# Power_System.net
KiCad netlist of a schematic drawn in Altium Designer
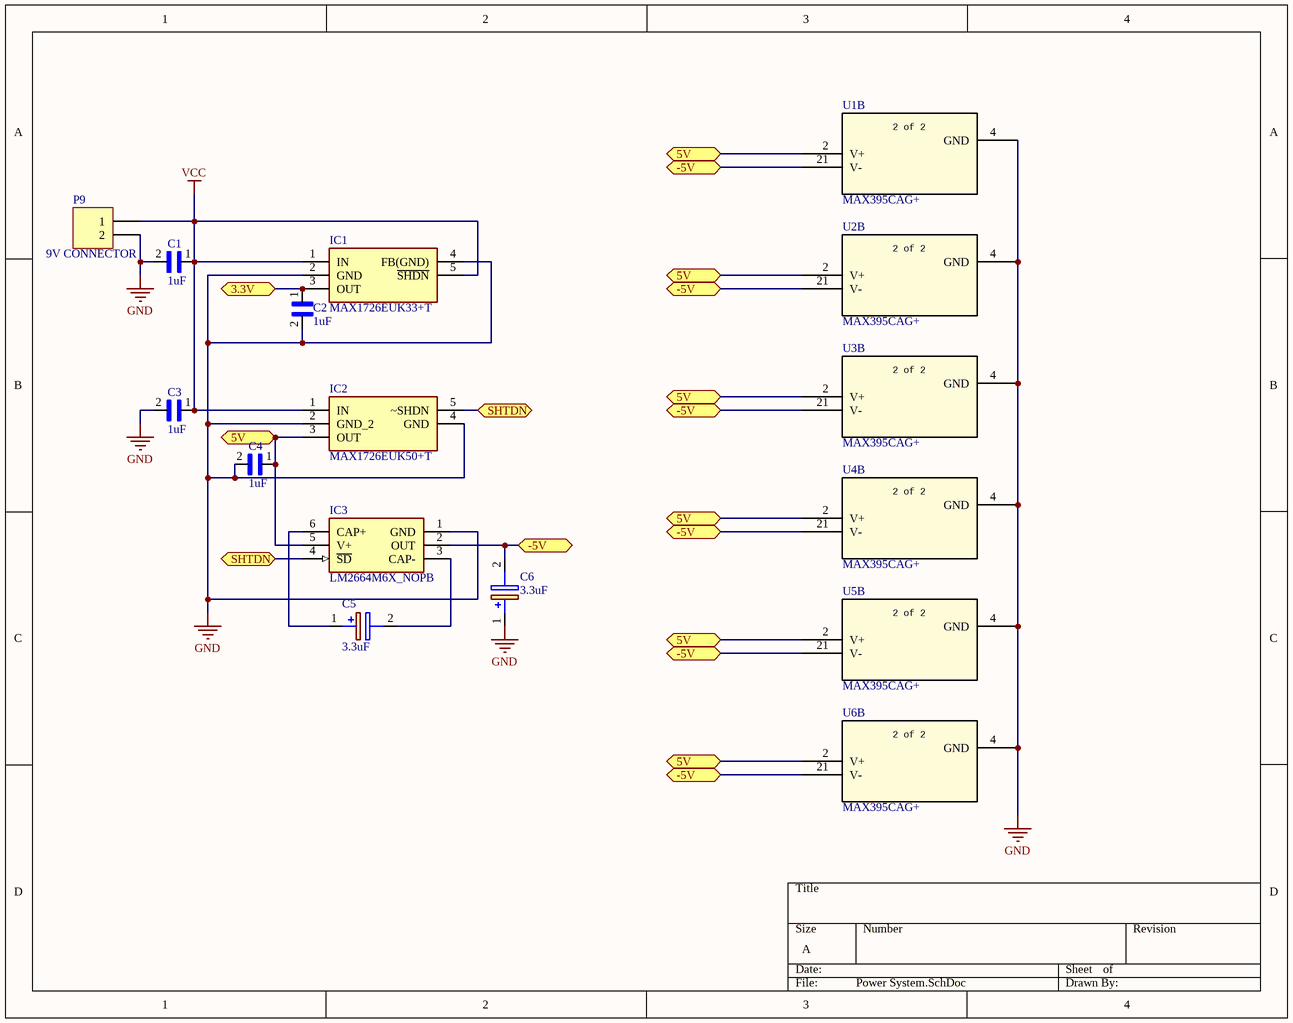
[diagram p0: Power System.SchDoc]

(export (version "E")
  (design (tool "Eeschema 10.0.6"))
  (components
    (comp (ref "C1")
      (value "1uF")
      (footprint "CAPC2012X135N")
      (description "1ÂµF Â±10% 25V Ceramic Capacitor X7R 0805 _2012 Metric_")
      (fields (field (name "DIGI-KEY_PART_NUMBER") "587-6357-1-ND") (field (name "MF") "Taiyo Yuden"))
      (libsource (lib "TMK212B7105KGHTR") (part "TMK212B7105KGHTR"))
    )
    (comp (ref "C2")
      (value "1uF")
      (footprint "CAPC2012X135N")
      (description "1ÂµF Â±10% 25V Ceramic Capacitor X7R 0805 _2012 Metric_")
      (fields (field (name "DIGI-KEY_PART_NUMBER") "587-6357-1-ND") (field (name "MF") "Taiyo Yuden"))
      (libsource (lib "") (part "TMK212B7105KGHTR_1"))
    )
    (comp (ref "C3")
      (value "1uF")
      (footprint "CAPC2012X135N")
      (description "1ÂµF Â±10% 25V Ceramic Capacitor X7R 0805 _2012 Metric_")
      (fields (field (name "DIGI-KEY_PART_NUMBER") "587-6357-1-ND") (field (name "MF") "Taiyo Yuden"))
      (libsource (lib "TMK212B7105KGHTR") (part "TMK212B7105KGHTR"))
    )
    (comp (ref "C4")
      (value "1uF")
      (footprint "CAPC2012X135N")
      (description "1ÂµF Â±10% 25V Ceramic Capacitor X7R 0805 _2012 Metric_")
      (fields (field (name "DIGI-KEY_PART_NUMBER") "587-6357-1-ND") (field (name "MF") "Taiyo Yuden"))
      (libsource (lib "TMK212B7105KGHTR") (part "TMK212B7105KGHTR"))
    )
    (comp (ref "C5")
      (value "3.3uF")
      (footprint "SamacSys:CAPAE430X550N")
      (description "Capacitor Polarised")
      (fields
        (field (name "MANUFACTURER_PART_NUMBER") "16SVP3R3M")
        (field (name "MOUSER PART NUMBER") "667-16SVP3R3M")
      )
      (libsource (lib "*") (part "16SVP3R3M"))
    )
    (comp (ref "C6")
      (value "3.3uF")
      (footprint "SamacSys:CAPAE430X550N")
      (description "Capacitor Polarised")
      (fields
        (field (name "MANUFACTURER_PART_NUMBER") "16SVP3R3M")
        (field (name "MOUSER PART NUMBER") "667-16SVP3R3M")
      )
      (libsource (lib "") (part "16SVP3R3M_1"))
    )
    (comp (ref "IC1")
      (value "MAX1726EUK33+T")
      (footprint "SamacSys:SOT95P280X145-5N")
      (description "Integrated Circuit")
      (fields (field (name "MOUSER PART NUMBER") "700-MAX1726EUK33T"))
      (libsource (lib "*") (part "MAX1726EUK33+T"))
    )
    (comp (ref "IC2")
      (value "MAX1726EUK50+T")
      (footprint "SamacSys:SOT95P280X145-5N")
      (description "Integrated Circuit")
      (fields (field (name "MOUSER PART NUMBER") "700-MAX1726EUK50T"))
      (libsource (lib "*") (part "MAX1726EUK50+T"))
    )
    (comp (ref "IC3")
      (value "LM2664M6X_NOPB")
      (footprint "SamacSys:SOT95P280X145-6N")
      (description "Integrated Circuit")
      (fields
        (field (name "MANUFACTURER_PART_NUMBER") "LM2664M6X/NOPB")
        (field (name "MOUSER PART NUMBER") "926-LM2664M6X/NOPB")
      )
      (libsource (lib "*") (part "LM2664M6X_NOPB"))
    )
    (comp (ref "P9")
      (value "9V CONNECTOR")
      (footprint "HDR1X2")
      (description "Header, 2-Pin")
      (fields (field (name "PUBLISHER") "Altium Limited"))
      (libsource (lib "Miscellaneous Connectors") (part "Header 2"))
    )
    (comp (ref "U1")
      (value "MAX395CAG+")
      (footprint "21-0056C_24_MXM")
      (description "No Description Available")
      (fields (field (name "COPYRIGHT") "Copyright (C) 2018 Accelerated Designs. All rights reserved"))
      (libsource (lib "MAX395") (part "MAX395CAG+"))
    )
    (comp (ref "U2")
      (value "MAX395CAG+")
      (footprint "21-0056C_24_MXM")
      (description "No Description Available")
      (fields (field (name "COPYRIGHT") "Copyright (C) 2018 Accelerated Designs. All rights reserved"))
      (libsource (lib "MAX395") (part "MAX395CAG+"))
    )
    (comp (ref "U3")
      (value "MAX395CAG+")
      (footprint "21-0056C_24_MXM")
      (description "No Description Available")
      (fields (field (name "COPYRIGHT") "Copyright (C) 2018 Accelerated Designs. All rights reserved"))
      (libsource (lib "MAX395") (part "MAX395CAG+"))
    )
    (comp (ref "U4")
      (value "MAX395CAG+")
      (footprint "21-0056C_24_MXM")
      (description "No Description Available")
      (fields (field (name "COPYRIGHT") "Copyright (C) 2018 Accelerated Designs. All rights reserved"))
      (libsource (lib "MAX395") (part "MAX395CAG+"))
    )
    (comp (ref "U5")
      (value "MAX395CAG+")
      (footprint "21-0056C_24_MXM")
      (description "No Description Available")
      (fields (field (name "COPYRIGHT") "Copyright (C) 2018 Accelerated Designs. All rights reserved"))
      (libsource (lib "MAX395") (part "MAX395CAG+"))
    )
    (comp (ref "U6")
      (value "MAX395CAG+")
      (footprint "21-0056C_24_MXM")
      (description "No Description Available")
      (fields (field (name "COPYRIGHT") "Copyright (C) 2018 Accelerated Designs. All rights reserved"))
      (libsource (lib "MAX395") (part "MAX395CAG+"))
    )
  )
  (nets
    (net (code "1") (name "/-5V") (class "Default")
      (node (ref "C6") (pin "2") (pinfunction "-_2") (pintype "passive"))
      (node (ref "IC3") (pin "2") (pinfunction "OUT_2") (pintype "power_in"))
      (node (ref "U1") (pin "21") (pinfunction "V-_21") (pintype "power_in"))
      (node (ref "U2") (pin "21") (pinfunction "V-_21") (pintype "power_in"))
      (node (ref "U3") (pin "21") (pinfunction "V-_21") (pintype "power_in"))
      (node (ref "U4") (pin "21") (pinfunction "V-_21") (pintype "power_in"))
      (node (ref "U5") (pin "21") (pinfunction "V-_21") (pintype "power_in"))
      (node (ref "U6") (pin "21") (pinfunction "V-_21") (pintype "power_in"))
    )
    (net (code "2") (name "/3.3V") (class "Default")
      (node (ref "C2") (pin "1") (pinfunction "1_1") (pintype "passive"))
      (node (ref "IC1") (pin "3") (pinfunction "OUT_3") (pintype "passive"))
    )
    (net (code "3") (name "/5V") (class "Default")
      (node (ref "C4") (pin "1") (pinfunction "1_1") (pintype "passive"))
      (node (ref "IC2") (pin "3") (pinfunction "OUT_3") (pintype "passive"))
      (node (ref "IC3") (pin "5") (pinfunction "V+_5") (pintype "power_in"))
      (node (ref "U1") (pin "2") (pinfunction "V+_2") (pintype "power_in"))
      (node (ref "U2") (pin "2") (pinfunction "V+_2") (pintype "power_in"))
      (node (ref "U3") (pin "2") (pinfunction "V+_2") (pintype "power_in"))
      (node (ref "U4") (pin "2") (pinfunction "V+_2") (pintype "power_in"))
      (node (ref "U5") (pin "2") (pinfunction "V+_2") (pintype "power_in"))
      (node (ref "U6") (pin "2") (pinfunction "V+_2") (pintype "power_in"))
    )
    (net (code "4") (name "/SHTDN") (class "Default")
      (node (ref "IC2") (pin "5") (pinfunction "~SHDN_5") (pintype "passive"))
      (node (ref "IC3") (pin "4") (pinfunction "~{SD}_4") (pintype "input"))
    )
    (net (code "5") (name "GND") (class "Default")
      (node (ref "C1") (pin "2") (pinfunction "2_2") (pintype "passive"))
      (node (ref "C2") (pin "2") (pinfunction "2_2") (pintype "passive"))
      (node (ref "C3") (pin "2") (pinfunction "2_2") (pintype "passive"))
      (node (ref "C4") (pin "2") (pinfunction "2_2") (pintype "passive"))
      (node (ref "C6") (pin "1") (pinfunction "+_1") (pintype "passive"))
      (node (ref "IC1") (pin "2") (pinfunction "GND_2") (pintype "passive"))
      (node (ref "IC1") (pin "4") (pinfunction "FB(GND)_4") (pintype "passive"))
      (node (ref "IC2") (pin "2") (pinfunction "GND_2_2") (pintype "passive"))
      (node (ref "IC2") (pin "4") (pinfunction "GND_4") (pintype "passive"))
      (node (ref "IC3") (pin "1") (pinfunction "GND_1") (pintype "power_in"))
      (node (ref "P9") (pin "2") (pinfunction "2_2") (pintype "passive"))
      (node (ref "U1") (pin "4") (pinfunction "GND_4") (pintype "power_in"))
      (node (ref "U2") (pin "4") (pinfunction "GND_4") (pintype "power_in"))
      (node (ref "U3") (pin "4") (pinfunction "GND_4") (pintype "power_in"))
      (node (ref "U4") (pin "4") (pinfunction "GND_4") (pintype "power_in"))
      (node (ref "U5") (pin "4") (pinfunction "GND_4") (pintype "power_in"))
      (node (ref "U6") (pin "4") (pinfunction "GND_4") (pintype "power_in"))
    )
    (net (code "6") (name "Net-(C5-+)") (class "Default")
      (node (ref "C5") (pin "1") (pinfunction "+_1") (pintype "passive"))
      (node (ref "IC3") (pin "6") (pinfunction "CAP+_6") (pintype "power_in"))
    )
    (net (code "7") (name "Net-(C5--)") (class "Default")
      (node (ref "C5") (pin "2") (pinfunction "-_2") (pintype "passive"))
      (node (ref "IC3") (pin "3") (pinfunction "CAP-_3") (pintype "power_in"))
    )
    (net (code "8") (name "VCC") (class "Default")
      (node (ref "C1") (pin "1") (pinfunction "1_1") (pintype "passive"))
      (node (ref "C3") (pin "1") (pinfunction "1_1") (pintype "passive"))
      (node (ref "IC1") (pin "1") (pinfunction "IN_1") (pintype "passive"))
      (node (ref "IC1") (pin "5") (pinfunction "~{SHDN}_5") (pintype "passive"))
      (node (ref "IC2") (pin "1") (pinfunction "IN_1") (pintype "passive"))
      (node (ref "P9") (pin "1") (pinfunction "1_1") (pintype "passive"))
    )
  )
)
